# ir_shield.net
KiCad netlist of a schematic drawn in EAGLE
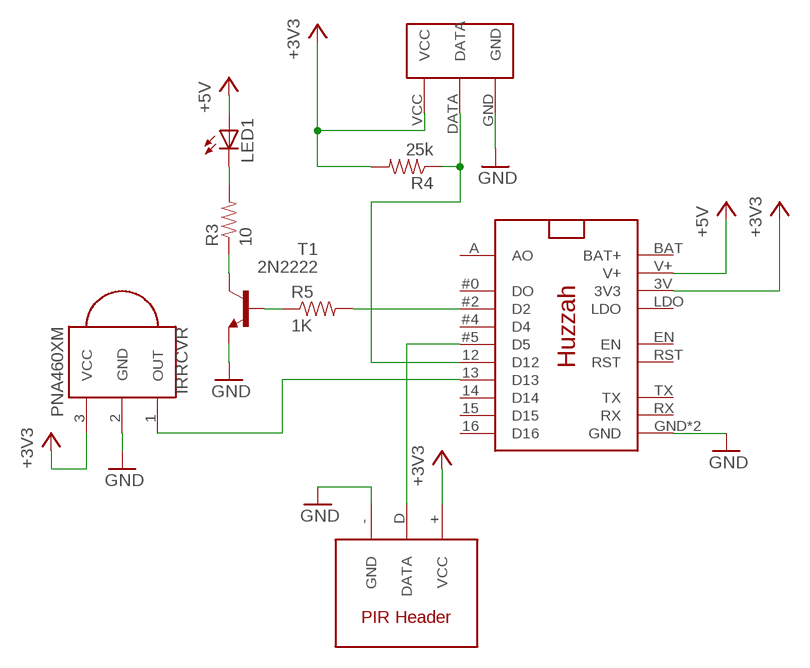
[diagram p0: schematic, sheet 1]

(export (version "E")
  (design (tool "Eeschema 10.0.6"))
  (components
    (comp (ref "IRRCVR")
      (value "PNA460XM")
      (footprint "eagle-import:PNA460XM")
      (libsource (lib "eagle-import") (part "PNA460XM"))
    )
    (comp (ref "LED1")
      (value "LEDIRL80A")
      (footprint "eagle-import:IRL80A")
      (libsource (lib "eagle-import") (part "LEDIRL80A"))
    )
    (comp (ref "R3")
      (value "10")
      (footprint "eagle-import:0402-RES")
      (libsource (lib "eagle-import") (part "RESISTOR0402-RES"))
    )
    (comp (ref "R4")
      (value "25k")
      (footprint "eagle-import:0402-RES")
      (libsource (lib "eagle-import") (part "RESISTOR0402-RES"))
    )
    (comp (ref "R5")
      (value "1K")
      (footprint "eagle-import:0402-RES")
      (libsource (lib "eagle-import") (part "RESISTOR0402-RES"))
    )
    (comp (ref "T1")
      (value "2N2222")
      (footprint "eagle-import:TO92-EBC-OVAL")
      (libsource (lib "eagle-import") (part "2N2222"))
    )
    (comp (ref "U$1")
      (value "HUZZAH_SHIELDOUTSIDE")
      (footprint "eagle-import:HUZZAH_OUTSIDE")
      (libsource (lib "eagle-import") (part "HUZZAH_SHIELDOUTSIDE"))
    )
    (comp (ref "U$3")
      (value "DHT11VERT")
      (footprint "eagle-import:DHT11-VERT")
      (libsource (lib "eagle-import") (part "DHT11VERT"))
    )
    (comp (ref "U$4")
      (value "PIR")
      (footprint "eagle-import:3_PIN_HEADER")
      (libsource (lib "eagle-import") (part "PIR"))
    )
  )
  (nets
    (net (code "1") (name "+3V3") (class "Default")
      (node (ref "IRRCVR") (pin "3") (pinfunction "VCC_3") (pintype "power_in"))
      (node (ref "R4") (pin "2") (pinfunction "2_2") (pintype "passive"))
      (node (ref "U$1") (pin "3V") (pinfunction "3V3_3V") (pintype "bidirectional"))
      (node (ref "U$3") (pin "VCC") (pinfunction "VCC_VCC") (pintype "bidirectional"))
      (node (ref "U$4") (pin "+") (pinfunction "VCC_+") (pintype "bidirectional"))
    )
    (net (code "2") (name "+5V") (class "Default")
      (node (ref "LED1") (pin "A") (pinfunction "A_A") (pintype "passive"))
      (node (ref "U$1") (pin "V+") (pinfunction "V+_V+") (pintype "bidirectional"))
    )
    (net (code "3") (name "GND") (class "Default")
      (node (ref "IRRCVR") (pin "2") (pinfunction "GND_2") (pintype "power_in"))
      (node (ref "T1") (pin "E") (pinfunction "E_E") (pintype "passive"))
      (node (ref "U$1") (pin "GND") (pinfunction "GND_GND") (pintype "bidirectional"))
      (node (ref "U$1") (pin "GND2") (pinfunction "GND_GND2") (pintype "bidirectional"))
      (node (ref "U$3") (pin "GND") (pinfunction "GND_GND") (pintype "bidirectional"))
      (node (ref "U$4") (pin "-") (pinfunction "GND_-") (pintype "bidirectional"))
    )
    (net (code "4") (name "Net-(IRRCVR-OUT)") (class "Default")
      (node (ref "IRRCVR") (pin "1") (pinfunction "OUT_1") (pintype "output"))
      (node (ref "U$1") (pin "13") (pinfunction "D13_13") (pintype "bidirectional"))
    )
    (net (code "5") (name "Net-(LED1-C)") (class "Default")
      (node (ref "LED1") (pin "K") (pinfunction "C_K") (pintype "passive"))
      (node (ref "R3") (pin "2") (pinfunction "2_2") (pintype "passive"))
    )
    (net (code "6") (name "Net-(R3-Pad1)") (class "Default")
      (node (ref "R3") (pin "1") (pinfunction "1_1") (pintype "passive"))
      (node (ref "T1") (pin "C") (pinfunction "C_C") (pintype "passive"))
    )
    (net (code "7") (name "Net-(R5-Pad1)") (class "Default")
      (node (ref "R5") (pin "1") (pinfunction "1_1") (pintype "passive"))
      (node (ref "T1") (pin "B") (pinfunction "B_B") (pintype "passive"))
    )
    (net (code "8") (name "Net-(U$1-D2)") (class "Default")
      (node (ref "R5") (pin "2") (pinfunction "2_2") (pintype "passive"))
      (node (ref "U$1") (pin "#2") (pinfunction "D2_#2") (pintype "bidirectional"))
    )
    (net (code "9") (name "Net-(U$1-D5)") (class "Default")
      (node (ref "U$1") (pin "#5") (pinfunction "D5_#5") (pintype "bidirectional"))
      (node (ref "U$4") (pin "D") (pinfunction "DATA_D") (pintype "bidirectional"))
    )
    (net (code "10") (name "Net-(U$1-D12)") (class "Default")
      (node (ref "R4") (pin "1") (pinfunction "1_1") (pintype "passive"))
      (node (ref "U$1") (pin "12") (pinfunction "D12_12") (pintype "bidirectional"))
      (node (ref "U$3") (pin "DATA") (pinfunction "DATA_DATA") (pintype "bidirectional"))
    )
    (net (code "11") (name "unconnected-(U$1-AO-PadA)") (class "Default")
      (node (ref "U$1") (pin "A") (pinfunction "AO_A") (pintype "bidirectional"))
    )
    (net (code "12") (name "unconnected-(U$1-BAT+-PadBAT)") (class "Default")
      (node (ref "U$1") (pin "BAT") (pinfunction "BAT+_BAT") (pintype "bidirectional"))
    )
    (net (code "13") (name "unconnected-(U$1-D4-Pad#4)") (class "Default")
      (node (ref "U$1") (pin "#4") (pinfunction "D4_#4") (pintype "bidirectional"))
    )
    (net (code "14") (name "unconnected-(U$1-D14-Pad14)") (class "Default")
      (node (ref "U$1") (pin "14") (pinfunction "D14_14") (pintype "bidirectional"))
    )
    (net (code "15") (name "unconnected-(U$1-D15-Pad15)") (class "Default")
      (node (ref "U$1") (pin "15") (pinfunction "D15_15") (pintype "bidirectional"))
    )
    (net (code "16") (name "unconnected-(U$1-D16-Pad16)") (class "Default")
      (node (ref "U$1") (pin "16") (pinfunction "D16_16") (pintype "bidirectional"))
    )
    (net (code "17") (name "unconnected-(U$1-DO-Pad#0)") (class "Default")
      (node (ref "U$1") (pin "#0") (pinfunction "DO_#0") (pintype "bidirectional"))
    )
    (net (code "18") (name "unconnected-(U$1-PadEN)") (class "Default")
      (node (ref "U$1") (pin "EN") (pinfunction "EN_EN") (pintype "bidirectional"))
    )
    (net (code "19") (name "unconnected-(U$1-PadLDO)") (class "Default")
      (node (ref "U$1") (pin "LDO") (pinfunction "LDO_LDO") (pintype "bidirectional"))
    )
    (net (code "20") (name "unconnected-(U$1-PadRST)") (class "Default")
      (node (ref "U$1") (pin "RST") (pinfunction "RST_RST") (pintype "bidirectional"))
    )
    (net (code "21") (name "unconnected-(U$1-PadRX)") (class "Default")
      (node (ref "U$1") (pin "RX") (pinfunction "RX_RX") (pintype "bidirectional"))
    )
    (net (code "22") (name "unconnected-(U$1-PadTX)") (class "Default")
      (node (ref "U$1") (pin "TX") (pinfunction "TX_TX") (pintype "bidirectional"))
    )
  )
)
